# Schematic.net
KiCad netlist of a schematic drawn in Altium Designer
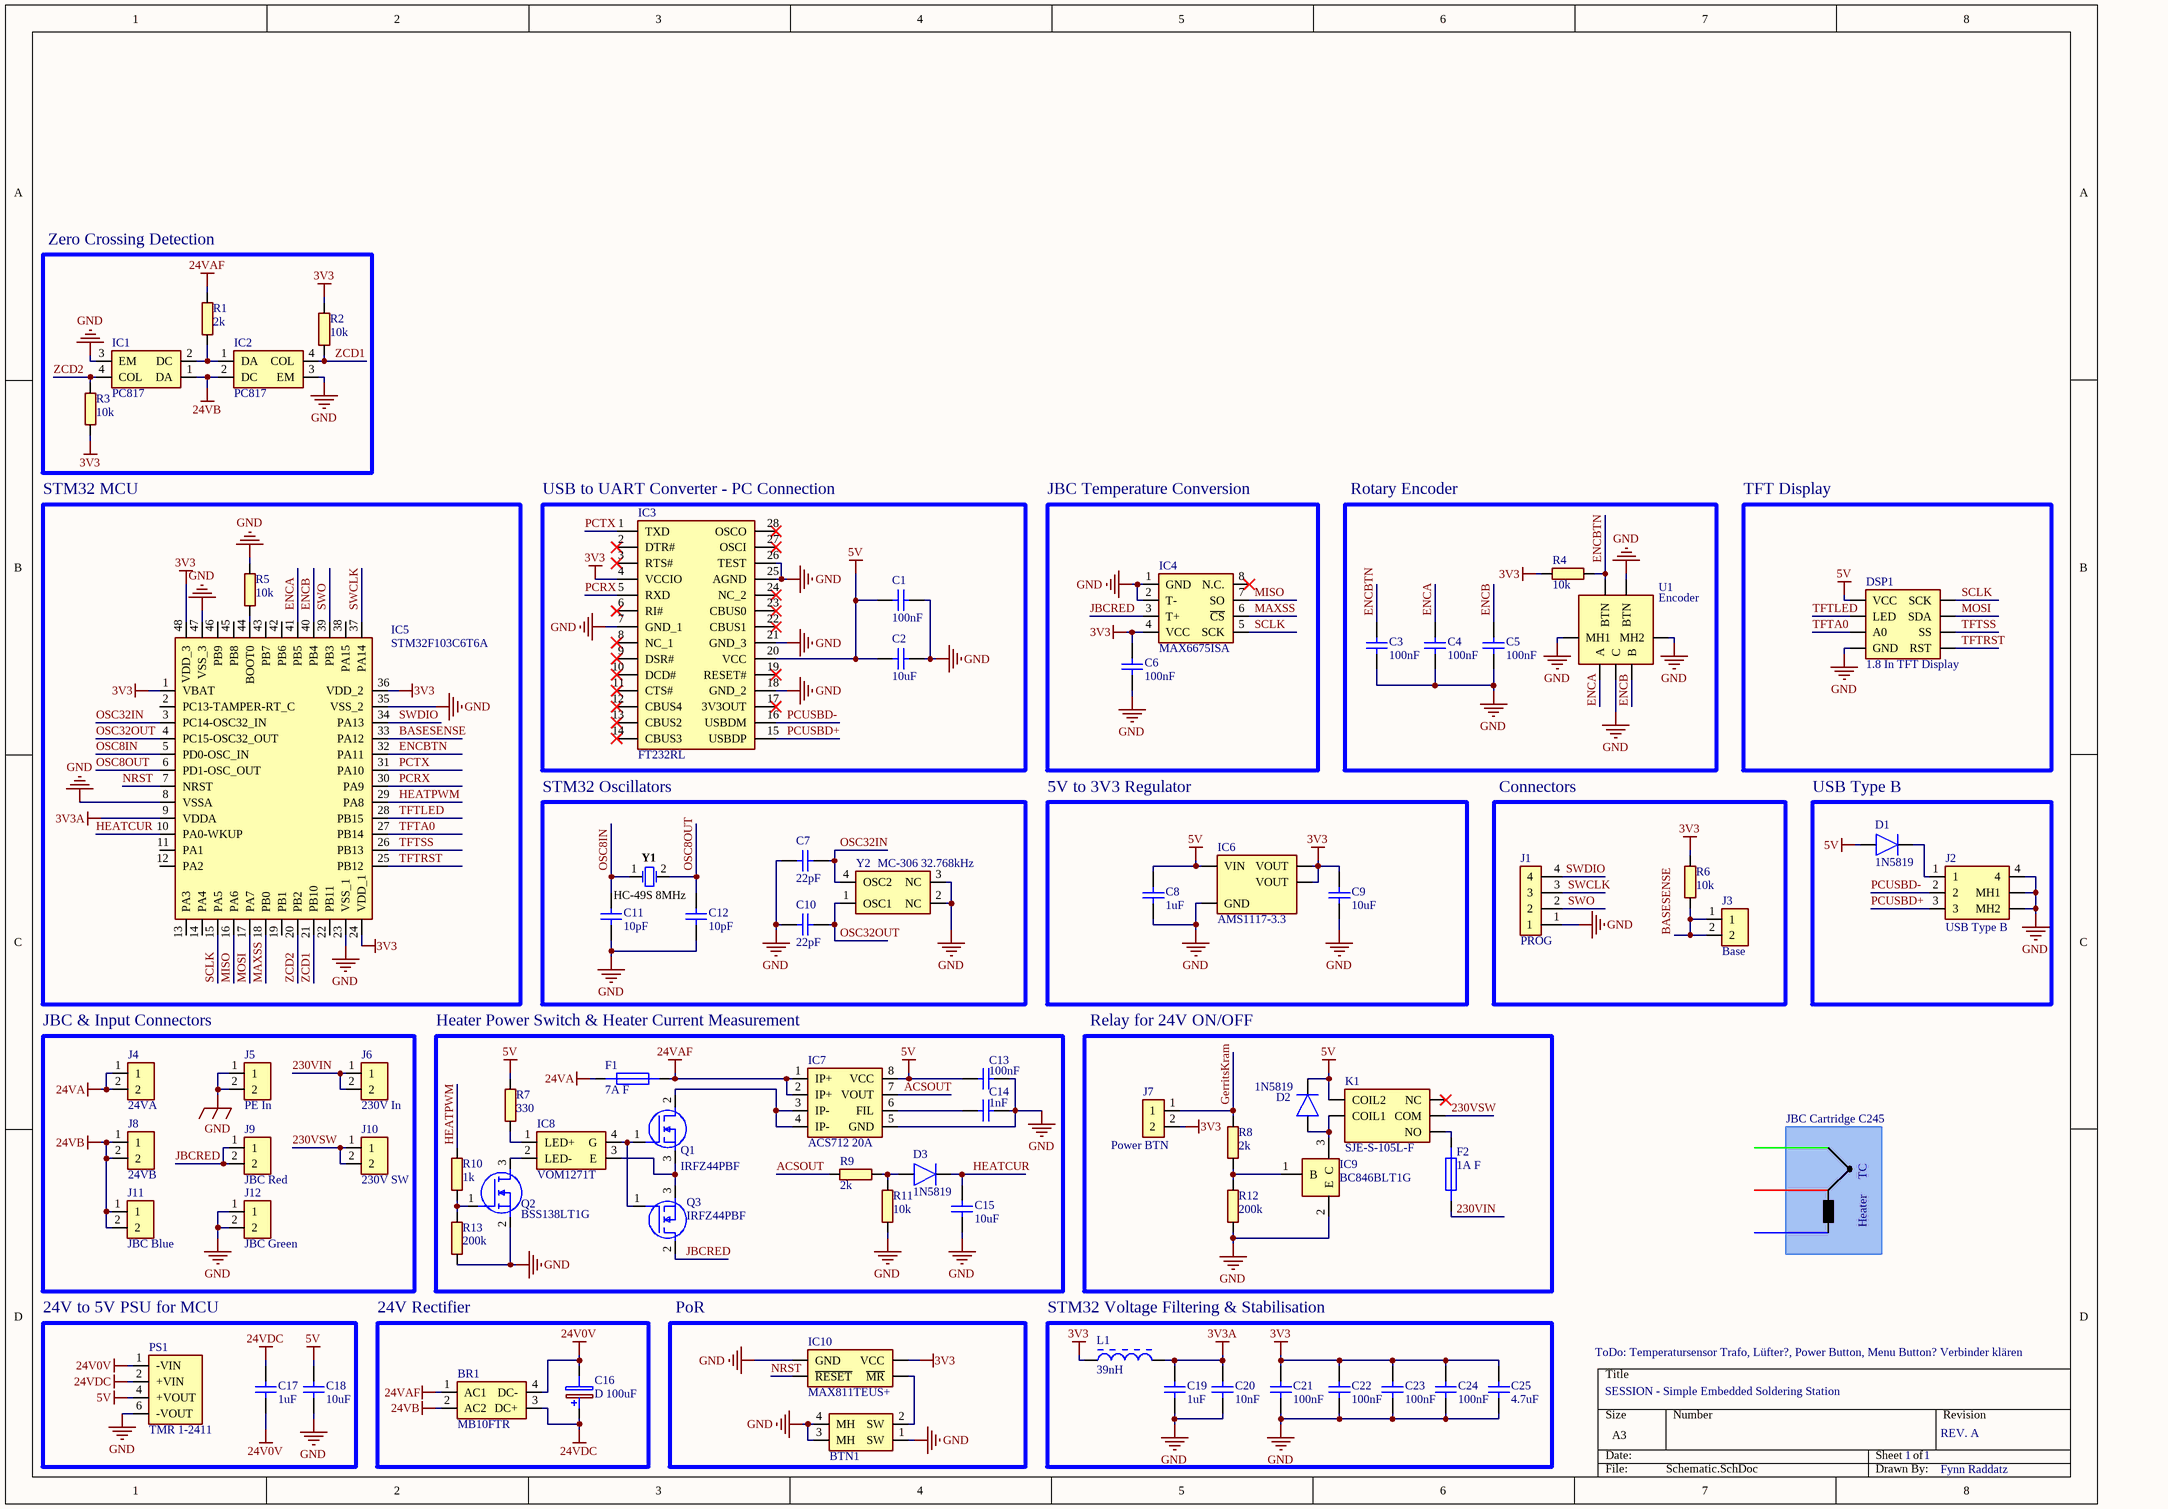
[diagram p0: Schematic.SchDoc]

(export (version "E")
  (design (tool "Eeschema 10.0.6"))
  (components
    (comp (ref "BR1")
      (value "MB10FTR")
      (footprint "SamacSys:SOP250P670X160-4N")
      (description "Bridge Rectifier")
      (libsource (lib "SamacSys") (part "MB10FTR"))
    )
    (comp (ref "BTN1")
      (value "SMD Button 6x6mm Angled")
      (footprint "SMD Button 6x6 Angled")
      (libsource (lib "SamacSys") (part "SMD Button 6x6mm Angled"))
    )
    (comp (ref "C1")
      (value "100nF")
      (footprint "SamacSys:CAPC2012 METRIC")
      (description "Capacitor")
      (fields (field (name "MANUFACTURER_PART_NUMBER") "CL21B104KACNNNC"))
      (libsource (lib "SamacSys") (part "CL21B104KACNNNC"))
    )
    (comp (ref "C2")
      (value "10uF")
      (footprint "SamacSys:CAPC2012 METRIC")
      (description "Capacitor")
      (fields (field (name "MANUFACTURER_PART_NUMBER") "CL21B104KACNNNC"))
      (libsource (lib "SamacSys") (part "CL21B104KACNNNC"))
    )
    (comp (ref "C3")
      (value "100nF")
      (footprint "SamacSys:CAPC2012 METRIC")
      (description "Capacitor")
      (fields (field (name "MANUFACTURER_PART_NUMBER") "CL21B104KACNNNC"))
      (libsource (lib "SamacSys") (part "CL21B104KACNNNC"))
    )
    (comp (ref "C4")
      (value "100nF")
      (footprint "SamacSys:CAPC2012 METRIC")
      (description "Capacitor")
      (fields (field (name "MANUFACTURER_PART_NUMBER") "CL21B104KACNNNC"))
      (libsource (lib "SamacSys") (part "CL21B104KACNNNC"))
    )
    (comp (ref "C5")
      (value "100nF")
      (footprint "SamacSys:CAPC2012 METRIC")
      (description "Capacitor")
      (fields (field (name "MANUFACTURER_PART_NUMBER") "CL21B104KACNNNC"))
      (libsource (lib "SamacSys") (part "CL21B104KACNNNC"))
    )
    (comp (ref "C6")
      (value "100nF")
      (footprint "SamacSys:CAPC2012 METRIC")
      (description "Capacitor")
      (fields (field (name "MANUFACTURER_PART_NUMBER") "CL21B104KACNNNC"))
      (libsource (lib "SamacSys") (part "CL21B104KACNNNC"))
    )
    (comp (ref "C7")
      (value "22pF")
      (footprint "SamacSys:CAPC2012 METRIC")
      (description "Capacitor")
      (fields (field (name "MANUFACTURER_PART_NUMBER") "CL21B104KACNNNC"))
      (libsource (lib "SamacSys") (part "CL21B104KACNNNC"))
    )
    (comp (ref "C8")
      (value "1uF")
      (footprint "SamacSys:CAPC2012 METRIC")
      (description "Capacitor")
      (fields (field (name "MANUFACTURER_PART_NUMBER") "CL21B104KACNNNC"))
      (libsource (lib "SamacSys") (part "CL21B104KACNNNC"))
    )
    (comp (ref "C9")
      (value "10uF")
      (footprint "SamacSys:CAPC2012 METRIC")
      (description "Capacitor")
      (fields (field (name "MANUFACTURER_PART_NUMBER") "CL21B104KACNNNC"))
      (libsource (lib "SamacSys") (part "CL21B104KACNNNC"))
    )
    (comp (ref "C10")
      (value "22pF")
      (footprint "SamacSys:CAPC2012 METRIC")
      (description "Capacitor")
      (fields (field (name "MANUFACTURER_PART_NUMBER") "CL21B104KACNNNC"))
      (libsource (lib "SamacSys") (part "CL21B104KACNNNC"))
    )
    (comp (ref "C11")
      (value "10pF")
      (footprint "SamacSys:CAPC2012 METRIC")
      (description "Capacitor")
      (fields (field (name "MANUFACTURER_PART_NUMBER") "CL21B104KACNNNC"))
      (libsource (lib "SamacSys") (part "CL21B104KACNNNC"))
    )
    (comp (ref "C12")
      (value "10pF")
      (footprint "SamacSys:CAPC2012 METRIC")
      (description "Capacitor")
      (fields (field (name "MANUFACTURER_PART_NUMBER") "CL21B104KACNNNC"))
      (libsource (lib "SamacSys") (part "CL21B104KACNNNC"))
    )
    (comp (ref "C13")
      (value "100nF")
      (footprint "SamacSys:CAPC2012 METRIC")
      (description "Capacitor")
      (fields (field (name "MANUFACTURER_PART_NUMBER") "CL21B104KACNNNC"))
      (libsource (lib "SamacSys") (part "CL21B104KACNNNC"))
    )
    (comp (ref "C14")
      (value "1nF")
      (footprint "SamacSys:CAPC2012 METRIC")
      (description "Capacitor")
      (fields (field (name "MANUFACTURER_PART_NUMBER") "CL21B104KACNNNC"))
      (libsource (lib "SamacSys") (part "CL21B104KACNNNC"))
    )
    (comp (ref "C15")
      (value "10uF")
      (footprint "SamacSys:CAPC2012 METRIC")
      (description "Capacitor")
      (fields (field (name "MANUFACTURER_PART_NUMBER") "CL21B104KACNNNC"))
      (libsource (lib "SamacSys") (part "CL21B104KACNNNC"))
    )
    (comp (ref "C16")
      (value "D 100uF")
      (footprint "TANTAL-D")
      (description "Capacitor Tantalum")
      (libsource (lib "SamacSys") (part "TANTAL-D"))
    )
    (comp (ref "C17")
      (value "1uF")
      (footprint "SamacSys:CAPC2012 METRIC")
      (description "Capacitor")
      (fields (field (name "MANUFACTURER_PART_NUMBER") "CL21B104KACNNNC"))
      (libsource (lib "SamacSys") (part "CL21B104KACNNNC"))
    )
    (comp (ref "C18")
      (value "10uF")
      (footprint "SamacSys:CAPC2012 METRIC")
      (description "Capacitor")
      (fields (field (name "MANUFACTURER_PART_NUMBER") "CL21B104KACNNNC"))
      (libsource (lib "SamacSys") (part "CL21B104KACNNNC"))
    )
    (comp (ref "C19")
      (value "1uF")
      (footprint "SamacSys:CAPC2012 METRIC")
      (description "Capacitor")
      (fields (field (name "MANUFACTURER_PART_NUMBER") "CL21B104KACNNNC"))
      (libsource (lib "SamacSys") (part "CL21B104KACNNNC"))
    )
    (comp (ref "C20")
      (value "10nF")
      (footprint "SamacSys:CAPC2012 METRIC")
      (description "Capacitor")
      (fields (field (name "MANUFACTURER_PART_NUMBER") "CL21B104KACNNNC"))
      (libsource (lib "SamacSys") (part "CL21B104KACNNNC"))
    )
    (comp (ref "C21")
      (value "100nF")
      (footprint "SamacSys:CAPC2012 METRIC")
      (description "Capacitor")
      (fields (field (name "MANUFACTURER_PART_NUMBER") "CL21B104KACNNNC"))
      (libsource (lib "SamacSys") (part "CL21B104KACNNNC"))
    )
    (comp (ref "C22")
      (value "100nF")
      (footprint "SamacSys:CAPC2012 METRIC")
      (description "Capacitor")
      (fields (field (name "MANUFACTURER_PART_NUMBER") "CL21B104KACNNNC"))
      (libsource (lib "SamacSys") (part "CL21B104KACNNNC"))
    )
    (comp (ref "C23")
      (value "100nF")
      (footprint "SamacSys:CAPC2012 METRIC")
      (description "Capacitor")
      (fields (field (name "MANUFACTURER_PART_NUMBER") "CL21B104KACNNNC"))
      (libsource (lib "SamacSys") (part "CL21B104KACNNNC"))
    )
    (comp (ref "C24")
      (value "100nF")
      (footprint "SamacSys:CAPC2012 METRIC")
      (description "Capacitor")
      (fields (field (name "MANUFACTURER_PART_NUMBER") "CL21B104KACNNNC"))
      (libsource (lib "SamacSys") (part "CL21B104KACNNNC"))
    )
    (comp (ref "C25")
      (value "4.7uF")
      (footprint "SamacSys:CAPC2012 METRIC")
      (description "Capacitor")
      (fields (field (name "MANUFACTURER_PART_NUMBER") "CL21B104KACNNNC"))
      (libsource (lib "SamacSys") (part "CL21B104KACNNNC"))
    )
    (comp (ref "D1")
      (value "1N5819")
      (footprint "SamacSys:SOD3716X145N")
      (description "Diode")
      (fields
        (field (name "MANUFACTURER_PART_NUMBER") "1N5819HW-7-F")
        (field (name "MOUSER PART NUMBER") "621-1N5819HW-F")
      )
      (libsource (lib "SamacSys") (part "1N5819HW-7-F"))
    )
    (comp (ref "D2")
      (value "1N5819")
      (footprint "SamacSys:SOD3716X145N")
      (description "Diode")
      (fields
        (field (name "MANUFACTURER_PART_NUMBER") "1N5819HW-7-F")
        (field (name "MOUSER PART NUMBER") "621-1N5819HW-F")
      )
      (libsource (lib "SamacSys") (part "1N5819HW-7-F"))
    )
    (comp (ref "D3")
      (value "1N5819")
      (footprint "SamacSys:SOD3716X145N")
      (description "Diode")
      (fields
        (field (name "MANUFACTURER_PART_NUMBER") "1N5819HW-7-F")
        (field (name "MOUSER PART NUMBER") "621-1N5819HW-F")
      )
      (libsource (lib "SamacSys") (part "1N5819HW-7-F"))
    )
    (comp (ref "DSP1")
      (value "1.8 In TFT Display")
      (footprint "1.8 Inch TFT Display")
      (description "Display")
      (libsource (lib "SamacSys") (part "TFT Display 1.8In SPI"))
    )
    (comp (ref "F1")
      (value "7A F")
      (footprint "Fuse Holder 5x20mm")
      (libsource (lib "SamacSys") (part "Fuse Holder 5x20mm"))
    )
    (comp (ref "F2")
      (value "1A F")
      (footprint "Fuse Holder 5x20mm")
      (libsource (lib "") (part "Fuse Holder 5x20mm_1"))
    )
    (comp (ref "IC1")
      (value "PC817")
      (footprint "SamacSys:SOP254P975X460-4N")
      (description "Integrated Circuit")
      (fields (field (name "MANUFACTURER_PART_NUMBER") "PC817X2NIP0F"))
      (libsource (lib "") (part "PC817X2NIP0F_1"))
    )
    (comp (ref "IC2")
      (value "PC817")
      (footprint "SamacSys:SOP254P975X460-4N")
      (description "Integrated Circuit")
      (fields (field (name "MANUFACTURER_PART_NUMBER") "PC817X2NIP0F"))
      (libsource (lib "SamacSys") (part "PC817X2NIP0F"))
    )
    (comp (ref "IC3")
      (value "FT232RL")
      (footprint "SamacSys:SOP65P778X200-28N")
      (description "Integrated Circuit")
      (libsource (lib "SamacSys") (part "FT232RL"))
    )
    (comp (ref "IC4")
      (value "MAX6675ISA")
      (footprint "SamacSys:SOIC127P600X175-8N")
      (description "Integrated Circuit")
      (libsource (lib "SamacSys") (part "MAX6675ISA"))
    )
    (comp (ref "IC5")
      (value "STM32F103C6T6A")
      (footprint "SamacSys:QFP50P900X900X160-48N")
      (description "Integrated Circuit")
      (fields (field (name "MOUSER PART NUMBER") "511-STM32F103C6T6A"))
      (libsource (lib "SamacSys") (part "STM32F103C6T6A"))
    )
    (comp (ref "IC6")
      (value "AMS1117-3.3")
      (footprint "SamacSys:SOT229P700X180-4N")
      (description "Integrated Circuit")
      (libsource (lib "SamacSys") (part "AMS1117-3.3"))
    )
    (comp (ref "IC7")
      (value "ACS712 20A")
      (footprint "SamacSys:SOIC127P600X175-8N")
      (description "Integrated Circuit")
      (fields (field (name "MANUFACTURER_PART_NUMBER") "ACS712ELCTR-05B-T"))
      (libsource (lib "SamacSys") (part "ACS712ELCTR-05B-T"))
    )
    (comp (ref "IC8")
      (value "VOM1271T")
      (footprint "SamacSys:SOP254P675X240-4N")
      (description "Integrated Circuit")
      (fields (field (name "MOUSER PART NUMBER") "78-VOM1271T"))
      (libsource (lib "SamacSys") (part "VOM1271T"))
    )
    (comp (ref "IC9")
      (value "BC846BLT1G")
      (footprint "SamacSys:SOT96P237X111-3N")
      (description "Integrated Circuit")
      (fields (field (name "MOUSER PART NUMBER") "863-BC846BLT1G"))
      (libsource (lib "SamacSys") (part "BC846BLT1G"))
    )
    (comp (ref "IC10")
      (value "MAX811TEUS+")
      (footprint "SamacSys:MAX811REUST")
      (description "Integrated Circuit")
      (libsource (lib "SamacSys") (part "MAX811TEUS+"))
    )
    (comp (ref "J1")
      (value "PROG")
      (footprint "SamacSys:HDRV4W95P0X254_1X4_1016X254X854P")
      (description "Connector")
      (fields
        (field (name "MANUFACTURER_PART_NUMBER") "61300411121")
        (field (name "MOUSER PART NUMBER") "710-61300411121")
      )
      (libsource (lib "SamacSys") (part "61300411121"))
    )
    (comp (ref "J2")
      (value "USB Type B")
      (footprint "SamacSys:SS52300001")
      (description "Connector")
      (fields
        (field (name "MANUFACTURER_PART_NUMBER") "SS-52300-001")
        (field (name "MOUSER PART NUMBER") "530-SS-52300-001")
      )
      (libsource (lib "SamacSys") (part "USB Type B Connector"))
    )
    (comp (ref "J3")
      (value "Base")
      (footprint "SamacSys:2 Pin Header BIG PADS")
      (description "Connector")
      (fields
        (field (name "MANUFACTURER_PART_NUMBER") "61300211121")
        (field (name "MOUSER PART NUMBER") "710-61300211121")
      )
      (libsource (lib "SamacSys") (part "2 Pin Header Big Pad"))
    )
    (comp (ref "J4")
      (value "24VA")
      (footprint "SamacSys:2 Pin Header BIG PADS")
      (description "Connector")
      (fields
        (field (name "MANUFACTURER_PART_NUMBER") "61300211121")
        (field (name "MOUSER PART NUMBER") "710-61300211121")
      )
      (libsource (lib "SamacSys") (part "2 Pin Header Big Pad"))
    )
    (comp (ref "J5")
      (value "PE In")
      (footprint "SamacSys:2 Pin Header BIG PADS")
      (description "Connector")
      (fields
        (field (name "MANUFACTURER_PART_NUMBER") "61300211121")
        (field (name "MOUSER PART NUMBER") "710-61300211121")
      )
      (libsource (lib "SamacSys") (part "2 Pin Header Big Pad"))
    )
    (comp (ref "J6")
      (value "230V In")
      (footprint "SamacSys:2 Pin Header BIG PADS")
      (description "Connector")
      (fields
        (field (name "MANUFACTURER_PART_NUMBER") "61300211121")
        (field (name "MOUSER PART NUMBER") "710-61300211121")
      )
      (libsource (lib "SamacSys") (part "2 Pin Header Big Pad"))
    )
    (comp (ref "J7")
      (value "Power BTN")
      (footprint "SamacSys:HDRV2W110P0X254_1X2_508X254X854P")
      (description "Connector")
      (fields
        (field (name "MANUFACTURER_PART_NUMBER") "61300211121")
        (field (name "MOUSER PART NUMBER") "710-61300211121")
      )
      (libsource (lib "SamacSys") (part "61300211121"))
    )
    (comp (ref "J8")
      (value "24VB")
      (footprint "SamacSys:2 Pin Header BIG PADS")
      (description "Connector")
      (fields
        (field (name "MANUFACTURER_PART_NUMBER") "61300211121")
        (field (name "MOUSER PART NUMBER") "710-61300211121")
      )
      (libsource (lib "SamacSys") (part "2 Pin Header Big Pad"))
    )
    (comp (ref "J9")
      (value "JBC Red")
      (footprint "SamacSys:2 Pin Header BIG PADS")
      (description "Connector")
      (fields
        (field (name "MANUFACTURER_PART_NUMBER") "61300211121")
        (field (name "MOUSER PART NUMBER") "710-61300211121")
      )
      (libsource (lib "SamacSys") (part "2 Pin Header Big Pad"))
    )
    (comp (ref "J10")
      (value "230V SW")
      (footprint "SamacSys:2 Pin Header BIG PADS")
      (description "Connector")
      (fields
        (field (name "MANUFACTURER_PART_NUMBER") "61300211121")
        (field (name "MOUSER PART NUMBER") "710-61300211121")
      )
      (libsource (lib "SamacSys") (part "2 Pin Header Big Pad"))
    )
    (comp (ref "J11")
      (value "JBC Blue")
      (footprint "SamacSys:2 Pin Header BIG PADS")
      (description "Connector")
      (fields
        (field (name "MANUFACTURER_PART_NUMBER") "61300211121")
        (field (name "MOUSER PART NUMBER") "710-61300211121")
      )
      (libsource (lib "SamacSys") (part "2 Pin Header Big Pad"))
    )
    (comp (ref "J12")
      (value "JBC Green")
      (footprint "SamacSys:2 Pin Header BIG PADS")
      (description "Connector")
      (fields
        (field (name "MANUFACTURER_PART_NUMBER") "61300211121")
        (field (name "MOUSER PART NUMBER") "710-61300211121")
      )
      (libsource (lib "SamacSys") (part "2 Pin Header Big Pad"))
    )
    (comp (ref "K1")
      (value "SJE-S-105L-F")
      (footprint "SamacSys:SJES105LF")
      (description "Relay or Contactor")
      (libsource (lib "SamacSys") (part "SJE-S-105L-F"))
    )
    (comp (ref "L1")
      (value "39nH")
      (footprint "LIRD-LI0805H151R-10-2_V")
      (description "Chip Bead, 100 MHz, 5 A, -40 to 125 degC, 2-Pin SMD (0805), RoHS, Tape and Reel")
      (fields (field (name "MANUFACTURER") "Laird"))
      (libsource (lib "Altium Content Vault") (part "IND-FB-2"))
    )
    (comp (ref "PS1")
      (value "TMR 1-2411")
      (footprint "SamacSys:TMR10511")
      (description "Power Supply")
      (fields (field (name "MOUSER PART NUMBER") "495-TMR-1-2411"))
      (libsource (lib "SamacSys") (part "TMR_1-2411"))
    )
    (comp (ref "Q1")
      (value "IRFZ44PBF")
      (footprint "SamacSys:TO254P465X1024X2050-3P")
      (description "MOSFET (N-Channel)")
      (fields (field (name "MOUSER PART NUMBER") "844-IRFZ44PBF"))
      (libsource (lib "SamacSys") (part "IRFZ44PBF"))
    )
    (comp (ref "Q2")
      (value "BSS138LT1G")
      (footprint "SamacSys:SOT96P237X111-3N")
      (description "MOSFET (N-Channel)")
      (fields (field (name "MOUSER PART NUMBER") "863-BSS138LT1G"))
      (libsource (lib "SamacSys") (part "BSS138LT1G"))
    )
    (comp (ref "Q3")
      (value "IRFZ44PBF")
      (footprint "SamacSys:TO254P465X1024X2050-3P")
      (description "MOSFET (N-Channel)")
      (fields (field (name "MOUSER PART NUMBER") "844-IRFZ44PBF"))
      (libsource (lib "SamacSys") (part "IRFZ44PBF"))
    )
    (comp (ref "R1")
      (value "2k")
      (footprint "SamacSys:RESC2012X65N")
      (description "Resistor")
      (fields (field (name "MANUFACTURER_PART_NUMBER") "RMCF0805ZT0R00"))
      (libsource (lib "SamacSys") (part "Res 0805"))
    )
    (comp (ref "R2")
      (value "10k")
      (footprint "SamacSys:RESC2012X65N")
      (description "Resistor")
      (fields (field (name "MANUFACTURER_PART_NUMBER") "RMCF0805ZT0R00"))
      (libsource (lib "") (part "Res 0805_1"))
    )
    (comp (ref "R3")
      (value "10k")
      (footprint "SamacSys:RESC2012X65N")
      (description "Resistor")
      (fields (field (name "MANUFACTURER_PART_NUMBER") "RMCF0805ZT0R00"))
      (libsource (lib "SamacSys") (part "Res 0805"))
    )
    (comp (ref "R4")
      (value "10k")
      (footprint "SamacSys:RESC2012X65N")
      (description "Resistor")
      (fields (field (name "MANUFACTURER_PART_NUMBER") "RMCF0805ZT0R00"))
      (libsource (lib "") (part "Res 0805_2"))
    )
    (comp (ref "R5")
      (value "10k")
      (footprint "SamacSys:RESC2012X65N")
      (description "Resistor")
      (fields (field (name "MANUFACTURER_PART_NUMBER") "RMCF0805ZT0R00"))
      (libsource (lib "SamacSys") (part "Res 0805"))
    )
    (comp (ref "R6")
      (value "10k")
      (footprint "SamacSys:RESC2012X65N")
      (description "Resistor")
      (fields (field (name "MANUFACTURER_PART_NUMBER") "RMCF0805ZT0R00"))
      (libsource (lib "") (part "Res 0805_1"))
    )
    (comp (ref "R7")
      (value "330")
      (footprint "SamacSys:RESC2012X65N")
      (description "Resistor")
      (fields (field (name "MANUFACTURER_PART_NUMBER") "RMCF0805ZT0R00"))
      (libsource (lib "SamacSys") (part "Res 0805"))
    )
    (comp (ref "R8")
      (value "2k")
      (footprint "SamacSys:RESC2012X65N")
      (description "Resistor")
      (fields (field (name "MANUFACTURER_PART_NUMBER") "RMCF0805ZT0R00"))
      (libsource (lib "SamacSys") (part "Res 0805"))
    )
    (comp (ref "R9")
      (value "2k")
      (footprint "SamacSys:RESC2012X65N")
      (description "Resistor")
      (fields (field (name "MANUFACTURER_PART_NUMBER") "RMCF0805ZT0R00"))
      (libsource (lib "") (part "Res 0805_2"))
    )
    (comp (ref "R10")
      (value "1k")
      (footprint "SamacSys:RESC2012X65N")
      (description "Resistor")
      (fields (field (name "MANUFACTURER_PART_NUMBER") "RMCF0805ZT0R00"))
      (libsource (lib "SamacSys") (part "Res 0805"))
    )
    (comp (ref "R11")
      (value "10k")
      (footprint "SamacSys:RESC2012X65N")
      (description "Resistor")
      (fields (field (name "MANUFACTURER_PART_NUMBER") "RMCF0805ZT0R00"))
      (libsource (lib "") (part "Res 0805_1"))
    )
    (comp (ref "R12")
      (value "200k")
      (footprint "SamacSys:RESC2012X65N")
      (description "Resistor")
      (fields (field (name "MANUFACTURER_PART_NUMBER") "RMCF0805ZT0R00"))
      (libsource (lib "SamacSys") (part "Res 0805"))
    )
    (comp (ref "R13")
      (value "200k")
      (footprint "SamacSys:RESC2012X65N")
      (description "Resistor")
      (fields (field (name "MANUFACTURER_PART_NUMBER") "RMCF0805ZT0R00"))
      (libsource (lib "SamacSys") (part "Res 0805"))
    )
    (comp (ref "U1")
      (value "Encoder")
      (footprint "SamacSys:EC11B152442D")
      (fields (field (name "MANUFACTURER_PART_NUMBER") "EC11B152442D"))
      (libsource (lib "SamacSys") (part "EC11B152442D"))
    )
    (comp (ref "Y1")
      (value "HC-49S 8MHz")
      (footprint "FOX-HC49SDLF_V")
      (description "Resistance Weld Crystal, 8 MHz, +/- 30 ppm, -20 to 70 degC, 2-Pin SMD, RoHS, Tape and Reel")
      (fields (field (name "MANUFACTURER") "FOX Electronics") (field (name "TOLERANCE") "50ppm"))
      (libsource (lib "Altium Content Vault") (part "XTAL-1-2-2"))
    )
    (comp (ref "Y2")
      (value "MC-306 32.768kHz")
      (footprint "SamacSys:MC306327680KA3ROHS")
      (description "Crystal or Oscillator")
      (fields
        (field (name "MANUFACTURER_PART_NUMBER") "MC-306 32.7680K-A3:ROHS")
        (field (name "MOUSER PART NUMBER") "732-MC306-32.7KA3R")
      )
      (libsource (lib "SamacSys") (part "MC-306_32.7680K-A3_ROHS"))
    )
  )
  (nets
    (net (code "1") (name "/230VIN") (class "Default")
      (node (ref "F2") (pin "1") (pinfunction "F1_1") (pintype "passive"))
      (node (ref "J6") (pin "1") (pinfunction "1_1") (pintype "passive"))
      (node (ref "J6") (pin "2") (pinfunction "2_2") (pintype "passive"))
    )
    (net (code "2") (name "/230VSW") (class "Default")
      (node (ref "J10") (pin "1") (pinfunction "1_1") (pintype "passive"))
      (node (ref "J10") (pin "2") (pinfunction "2_2") (pintype "passive"))
      (node (ref "K1") (pin "3") (pinfunction "COM_3") (pintype "passive"))
    )
    (net (code "3") (name "/ACSOUT") (class "Default")
      (node (ref "IC7") (pin "7") (pinfunction "VOUT_7") (pintype "passive"))
      (node (ref "R9") (pin "2") (pinfunction "2_2") (pintype "passive"))
    )
    (net (code "4") (name "/BASESENSE") (class "Default")
      (node (ref "IC5") (pin "33") (pinfunction "PA12_33") (pintype "passive"))
      (node (ref "J3") (pin "1") (pinfunction "1_1") (pintype "passive"))
      (node (ref "J3") (pin "2") (pinfunction "2_2") (pintype "passive"))
      (node (ref "R6") (pin "2") (pinfunction "2_2") (pintype "passive"))
    )
    (net (code "5") (name "/ENCA") (class "Default")
      (node (ref "C4") (pin "2") (pinfunction "2_2") (pintype "passive"))
      (node (ref "IC5") (pin "41") (pinfunction "PB5_41") (pintype "passive"))
      (node (ref "U1") (pin "A") (pinfunction "A_A") (pintype "passive"))
    )
    (net (code "6") (name "/ENCB") (class "Default")
      (node (ref "C5") (pin "2") (pinfunction "2_2") (pintype "passive"))
      (node (ref "IC5") (pin "40") (pinfunction "PB4_40") (pintype "passive"))
      (node (ref "U1") (pin "B") (pinfunction "B_B") (pintype "passive"))
    )
    (net (code "7") (name "/ENCBTN") (class "Default")
      (node (ref "C3") (pin "2") (pinfunction "2_2") (pintype "passive"))
      (node (ref "IC5") (pin "32") (pinfunction "PA11_32") (pintype "passive"))
      (node (ref "R4") (pin "1") (pinfunction "1_1") (pintype "passive"))
      (node (ref "U1") (pin "MH3") (pinfunction "BTN_MH3") (pintype "passive"))
    )
    (net (code "8") (name "/GerritsKram") (class "Default")
      (node (ref "J7") (pin "1") (pinfunction "1_1") (pintype "passive"))
      (node (ref "R8") (pin "2") (pinfunction "2_2") (pintype "passive"))
    )
    (net (code "9") (name "/HEATCUR") (class "Default")
      (node (ref "C15") (pin "1") (pinfunction "1_1") (pintype "passive"))
      (node (ref "D3") (pin "1") (pinfunction "K_1") (pintype "passive"))
      (node (ref "IC5") (pin "10") (pinfunction "PA0-WKUP_10") (pintype "passive"))
    )
    (net (code "10") (name "/HEATPWM") (class "Default")
      (node (ref "IC5") (pin "29") (pinfunction "PA8_29") (pintype "passive"))
      (node (ref "R10") (pin "2") (pinfunction "2_2") (pintype "passive"))
    )
    (net (code "11") (name "/JBCRED") (class "Default")
      (node (ref "IC4") (pin "3") (pinfunction "T+_3") (pintype "passive"))
      (node (ref "J9") (pin "1") (pinfunction "1_1") (pintype "passive"))
      (node (ref "J9") (pin "2") (pinfunction "2_2") (pintype "passive"))
      (node (ref "Q3") (pin "2") (pinfunction "D_2") (pintype "passive"))
    )
    (net (code "12") (name "/MAXSS") (class "Default")
      (node (ref "IC4") (pin "6") (pinfunction "~{CS}_6") (pintype "passive"))
      (node (ref "IC5") (pin "18") (pinfunction "PB0_18") (pintype "passive"))
    )
    (net (code "13") (name "/MISO") (class "Default")
      (node (ref "IC4") (pin "7") (pinfunction "SO_7") (pintype "passive"))
      (node (ref "IC5") (pin "16") (pinfunction "PA6_16") (pintype "passive"))
    )
    (net (code "14") (name "/MOSI") (class "Default")
      (node (ref "DSP1") (pin "3") (pinfunction "SDA_3") (pintype "passive"))
      (node (ref "IC5") (pin "17") (pinfunction "PA7_17") (pintype "passive"))
    )
    (net (code "15") (name "/NRST") (class "Default")
      (node (ref "IC10") (pin "2") (pinfunction "~{RESET}_2") (pintype "passive"))
      (node (ref "IC5") (pin "7") (pinfunction "NRST_7") (pintype "passive"))
    )
    (net (code "16") (name "/OSC8IN") (class "Default")
      (node (ref "C11") (pin "2") (pinfunction "2_2") (pintype "passive"))
      (node (ref "IC5") (pin "5") (pinfunction "PD0-OSC_IN_5") (pintype "passive"))
      (node (ref "Y1") (pin "1") (pinfunction "1_1") (pintype "passive"))
    )
    (net (code "17") (name "/OSC8OUT") (class "Default")
      (node (ref "C12") (pin "2") (pinfunction "2_2") (pintype "passive"))
      (node (ref "IC5") (pin "6") (pinfunction "PD1-OSC_OUT_6") (pintype "passive"))
      (node (ref "Y1") (pin "2") (pinfunction "2_2") (pintype "passive"))
    )
    (net (code "18") (name "/OSC32IN") (class "Default")
      (node (ref "C7") (pin "1") (pinfunction "1_1") (pintype "passive"))
      (node (ref "IC5") (pin "3") (pinfunction "PC14-OSC32_IN_3") (pintype "passive"))
      (node (ref "Y2") (pin "4") (pinfunction "OSC2_4") (pintype "passive"))
    )
    (net (code "19") (name "/OSC32OUT") (class "Default")
      (node (ref "C10") (pin "1") (pinfunction "1_1") (pintype "passive"))
      (node (ref "IC5") (pin "4") (pinfunction "PC15-OSC32_OUT_4") (pintype "passive"))
      (node (ref "Y2") (pin "1") (pinfunction "OSC1_1") (pintype "passive"))
    )
    (net (code "20") (name "/PCRX") (class "Default")
      (node (ref "IC3") (pin "5") (pinfunction "RXD_5") (pintype "passive"))
      (node (ref "IC5") (pin "30") (pinfunction "PA9_30") (pintype "passive"))
    )
    (net (code "21") (name "/PCTX") (class "Default")
      (node (ref "IC3") (pin "1") (pinfunction "TXD_1") (pintype "passive"))
      (node (ref "IC5") (pin "31") (pinfunction "PA10_31") (pintype "passive"))
    )
    (net (code "22") (name "/PCUSBD+") (class "Default")
      (node (ref "IC3") (pin "15") (pinfunction "USBDP_15") (pintype "passive"))
      (node (ref "J2") (pin "3") (pinfunction "3_3") (pintype "passive"))
    )
    (net (code "23") (name "/PCUSBD-") (class "Default")
      (node (ref "IC3") (pin "16") (pinfunction "USBDM_16") (pintype "passive"))
      (node (ref "J2") (pin "2") (pinfunction "2_2") (pintype "passive"))
    )
    (net (code "24") (name "/SCLK") (class "Default")
      (node (ref "DSP1") (pin "2") (pinfunction "SCK_2") (pintype "passive"))
      (node (ref "IC4") (pin "5") (pinfunction "SCK_5") (pintype "passive"))
      (node (ref "IC5") (pin "15") (pinfunction "PA5_15") (pintype "passive"))
    )
    (net (code "25") (name "/SWCLK") (class "Default")
      (node (ref "IC5") (pin "37") (pinfunction "PA14_37") (pintype "passive"))
      (node (ref "J1") (pin "3") (pinfunction "3_3") (pintype "passive"))
    )
    (net (code "26") (name "/SWDIO") (class "Default")
      (node (ref "IC5") (pin "34") (pinfunction "PA13_34") (pintype "passive"))
      (node (ref "J1") (pin "4") (pinfunction "4_4") (pintype "passive"))
    )
    (net (code "27") (name "/SWO") (class "Default")
      (node (ref "IC5") (pin "39") (pinfunction "PB3_39") (pintype "passive"))
      (node (ref "J1") (pin "2") (pinfunction "2_2") (pintype "passive"))
    )
    (net (code "28") (name "/TFTA0") (class "Default")
      (node (ref "DSP1") (pin "4") (pinfunction "A0_4") (pintype "passive"))
      (node (ref "IC5") (pin "27") (pinfunction "PB14_27") (pintype "passive"))
    )
    (net (code "29") (name "/TFTLED") (class "Default")
      (node (ref "DSP1") (pin "1") (pinfunction "LED_1") (pintype "passive"))
      (node (ref "IC5") (pin "28") (pinfunction "PB15_28") (pintype "passive"))
    )
    (net (code "30") (name "/TFTRST") (class "Default")
      (node (ref "DSP1") (pin "5") (pinfunction "RST_5") (pintype "passive"))
      (node (ref "IC5") (pin "25") (pinfunction "PB12_25") (pintype "passive"))
    )
    (net (code "31") (name "/TFTSS") (class "Default")
      (node (ref "DSP1") (pin "6") (pinfunction "SS_6") (pintype "passive"))
      (node (ref "IC5") (pin "26") (pinfunction "PB13_26") (pintype "passive"))
    )
    (net (code "32") (name "/ZCD1") (class "Default")
      (node (ref "IC2") (pin "4") (pinfunction "COL_4") (pintype "passive"))
      (node (ref "IC5") (pin "21") (pinfunction "PB10_21") (pintype "passive"))
      (node (ref "R2") (pin "2") (pinfunction "2_2") (pintype "passive"))
    )
    (net (code "33") (name "/ZCD2") (class "Default")
      (node (ref "IC1") (pin "4") (pinfunction "COL_4") (pintype "passive"))
      (node (ref "IC5") (pin "20") (pinfunction "PB2_20") (pintype "passive"))
      (node (ref "R3") (pin "2") (pinfunction "2_2") (pintype "passive"))
    )
    (net (code "34") (name "3V3") (class "Default")
      (node (ref "C21") (pin "2") (pinfunction "2_2") (pintype "passive"))
      (node (ref "C22") (pin "2") (pinfunction "2_2") (pintype "passive"))
      (node (ref "C23") (pin "2") (pinfunction "2_2") (pintype "passive"))
      (node (ref "C24") (pin "2") (pinfunction "2_2") (pintype "passive"))
      (node (ref "C25") (pin "2") (pinfunction "2_2") (pintype "passive"))
      (node (ref "C6") (pin "2") (pinfunction "2_2") (pintype "passive"))
      (node (ref "C9") (pin "1") (pinfunction "1_1") (pintype "passive"))
      (node (ref "IC10") (pin "4") (pinfunction "VCC_4") (pintype "passive"))
      (node (ref "IC3") (pin "4") (pinfunction "VCCIO_4") (pintype "passive"))
      (node (ref "IC4") (pin "4") (pinfunction "VCC_4") (pintype "passive"))
      (node (ref "IC5") (pin "1") (pinfunction "VBAT_1") (pintype "passive"))
      (node (ref "IC5") (pin "24") (pinfunction "VDD_1_24") (pintype "passive"))
      (node (ref "IC5") (pin "36") (pinfunction "VDD_2_36") (pintype "passive"))
      (node (ref "IC5") (pin "48") (pinfunction "VDD_3_48") (pintype "passive"))
      (node (ref "IC6") (pin "2") (pinfunction "VOUT_2") (pintype "passive"))
      (node (ref "IC6") (pin "4") (pinfunction "VOUT_4") (pintype "passive"))
      (node (ref "J7") (pin "2") (pinfunction "2_2") (pintype "passive"))
      (node (ref "L1") (pin "1") (pinfunction "1_1") (pintype "passive"))
      (node (ref "R2") (pin "1") (pinfunction "1_1") (pintype "passive"))
      (node (ref "R3") (pin "1") (pinfunction "1_1") (pintype "passive"))
      (node (ref "R4") (pin "2") (pinfunction "2_2") (pintype "passive"))
      (node (ref "R6") (pin "1") (pinfunction "1_1") (pintype "passive"))
    )
    (net (code "35") (name "3V3A") (class "Default")
      (node (ref "C19") (pin "2") (pinfunction "2_2") (pintype "passive"))
      (node (ref "C20") (pin "2") (pinfunction "2_2") (pintype "passive"))
      (node (ref "IC5") (pin "9") (pinfunction "VDDA_9") (pintype "passive"))
      (node (ref "L1") (pin "2") (pinfunction "2_2") (pintype "passive"))
    )
    (net (code "36") (name "5V") (class "Default")
      (node (ref "C1") (pin "1") (pinfunction "1_1") (pintype "passive"))
      (node (ref "C13") (pin "2") (pinfunction "2_2") (pintype "passive"))
      (node (ref "C18") (pin "2") (pinfunction "2_2") (pintype "passive"))
      (node (ref "C2") (pin "1") (pinfunction "1_1") (pintype "passive"))
      (node (ref "C8") (pin "1") (pinfunction "1_1") (pintype "passive"))
      (node (ref "D1") (pin "2") (pinfunction "A_2") (pintype "passive"))
      (node (ref "D2") (pin "1") (pinfunction "K_1") (pintype "passive"))
      (node (ref "DSP1") (pin "8") (pinfunction "VCC_8") (pintype "passive"))
      (node (ref "IC3") (pin "20") (pinfunction "VCC_20") (pintype "passive"))
      (node (ref "IC6") (pin "3") (pinfunction "VIN_3") (pintype "passive"))
      (node (ref "IC7") (pin "8") (pinfunction "VCC_8") (pintype "passive"))
      (node (ref "K1") (pin "2") (pinfunction "COIL2_2") (pintype "passive"))
      (node (ref "PS1") (pin "4") (pinfunction "+VOUT_4") (pintype "passive"))
      (node (ref "R7") (pin "2") (pinfunction "2_2") (pintype "passive"))
    )
    (net (code "37") (name "24V0V") (class "Default")
      (node (ref "BR1") (pin "4") (pinfunction "DC-_4") (pintype "passive"))
      (node (ref "C16") (pin "2") (pinfunction "-_2") (pintype "passive"))
      (node (ref "C17") (pin "1") (pinfunction "1_1") (pintype "passive"))
      (node (ref "PS1") (pin "1") (pinfunction "-VIN_1") (pintype "passive"))
    )
    (net (code "38") (name "24VA") (class "Default")
      (node (ref "F1") (pin "1") (pinfunction "F1_1") (pintype "passive"))
      (node (ref "J4") (pin "1") (pinfunction "1_1") (pintype "passive"))
      (node (ref "J4") (pin "2") (pinfunction "2_2") (pintype "passive"))
    )
    (net (code "39") (name "24VAF") (class "Default")
      (node (ref "BR1") (pin "1") (pinfunction "AC1_1") (pintype "passive"))
      (node (ref "F1") (pin "2") (pinfunction "F2_2") (pintype "passive"))
      (node (ref "IC7") (pin "1") (pinfunction "IP+_1") (pintype "passive"))
      (node (ref "IC7") (pin "2") (pinfunction "IP+_2") (pintype "passive"))
      (node (ref "R1") (pin "2") (pinfunction "2_2") (pintype "passive"))
    )
    (net (code "40") (name "24VB") (class "Default")
      (node (ref "BR1") (pin "2") (pinfunction "AC2_2") (pintype "passive"))
      (node (ref "IC1") (pin "1") (pinfunction "DA_1") (pintype "passive"))
      (node (ref "IC2") (pin "2") (pinfunction "DC_2") (pintype "passive"))
      (node (ref "J11") (pin "1") (pinfunction "1_1") (pintype "passive"))
      (node (ref "J11") (pin "2") (pinfunction "2_2") (pintype "passive"))
      (node (ref "J8") (pin "1") (pinfunction "1_1") (pintype "passive"))
      (node (ref "J8") (pin "2") (pinfunction "2_2") (pintype "passive"))
    )
    (net (code "41") (name "24VDC") (class "Default")
      (node (ref "BR1") (pin "3") (pinfunction "DC+_3") (pintype "passive"))
      (node (ref "C16") (pin "1") (pinfunction "+_1") (pintype "passive"))
      (node (ref "C17") (pin "2") (pinfunction "2_2") (pintype "passive"))
      (node (ref "PS1") (pin "2") (pinfunction "+VIN_2") (pintype "passive"))
    )
    (net (code "42") (name "GND") (class "Default")
      (node (ref "BTN1") (pin "1") (pinfunction "SW_1") (pintype "passive"))
      (node (ref "BTN1") (pin "3") (pinfunction "MH_3") (pintype "passive"))
      (node (ref "BTN1") (pin "4") (pinfunction "MH_4") (pintype "passive"))
      (node (ref "C1") (pin "2") (pinfunction "2_2") (pintype "passive"))
      (node (ref "C10") (pin "2") (pinfunction "2_2") (pintype "passive"))
      (node (ref "C11") (pin "1") (pinfunction "1_1") (pintype "passive"))
      (node (ref "C12") (pin "1") (pinfunction "1_1") (pintype "passive"))
      (node (ref "C13") (pin "1") (pinfunction "1_1") (pintype "passive"))
      (node (ref "C14") (pin "1") (pinfunction "1_1") (pintype "passive"))
      (node (ref "C15") (pin "2") (pinfunction "2_2") (pintype "passive"))
      (node (ref "C18") (pin "1") (pinfunction "1_1") (pintype "passive"))
      (node (ref "C19") (pin "1") (pinfunction "1_1") (pintype "passive"))
      (node (ref "C2") (pin "2") (pinfunction "2_2") (pintype "passive"))
      (node (ref "C20") (pin "1") (pinfunction "1_1") (pintype "passive"))
      (node (ref "C21") (pin "1") (pinfunction "1_1") (pintype "passive"))
      (node (ref "C22") (pin "1") (pinfunction "1_1") (pintype "passive"))
      (node (ref "C23") (pin "1") (pinfunction "1_1") (pintype "passive"))
      (node (ref "C24") (pin "1") (pinfunction "1_1") (pintype "passive"))
      (node (ref "C25") (pin "1") (pinfunction "1_1") (pintype "passive"))
      (node (ref "C3") (pin "1") (pinfunction "1_1") (pintype "passive"))
      (node (ref "C4") (pin "1") (pinfunction "1_1") (pintype "passive"))
      (node (ref "C5") (pin "1") (pinfunction "1_1") (pintype "passive"))
      (node (ref "C6") (pin "1") (pinfunction "1_1") (pintype "passive"))
      (node (ref "C7") (pin "2") (pinfunction "2_2") (pintype "passive"))
      (node (ref "C8") (pin "2") (pinfunction "2_2") (pintype "passive"))
      (node (ref "C9") (pin "2") (pinfunction "2_2") (pintype "passive"))
      (node (ref "DSP1") (pin "7") (pinfunction "GND_7") (pintype "passive"))
      (node (ref "IC1") (pin "3") (pinfunction "EM_3") (pintype "passive"))
      (node (ref "IC10") (pin "1") (pinfunction "GND_1") (pintype "passive"))
      (node (ref "IC2") (pin "3") (pinfunction "EM_3") (pintype "passive"))
      (node (ref "IC3") (pin "18") (pinfunction "GND_2_18") (pintype "passive"))
      (node (ref "IC3") (pin "21") (pinfunction "GND_3_21") (pintype "passive"))
      (node (ref "IC3") (pin "25") (pinfunction "AGND_25") (pintype "passive"))
      (node (ref "IC3") (pin "26") (pinfunction "TEST_26") (pintype "passive"))
      (node (ref "IC3") (pin "7") (pinfunction "GND_1_7") (pintype "passive"))
      (node (ref "IC4") (pin "1") (pinfunction "GND_1") (pintype "passive"))
      (node (ref "IC4") (pin "2") (pinfunction "T-_2") (pintype "passive"))
      (node (ref "IC5") (pin "23") (pinfunction "VSS_1_23") (pintype "passive"))
      (node (ref "IC5") (pin "35") (pinfunction "VSS_2_35") (pintype "passive"))
      (node (ref "IC5") (pin "47") (pinfunction "VSS_3_47") (pintype "passive"))
      (node (ref "IC5") (pin "8") (pinfunction "VSSA_8") (pintype "passive"))
      (node (ref "IC6") (pin "1") (pinfunction "GND_1") (pintype "passive"))
      (node (ref "IC7") (pin "5") (pinfunction "GND_5") (pintype "passive"))
      (node (ref "IC9") (pin "2") (pinfunction "E_2") (pintype "passive"))
      (node (ref "J1") (pin "1") (pinfunction "1_1") (pintype "passive"))
      (node (ref "J12") (pin "1") (pinfunction "1_1") (pintype "passive"))
      (node (ref "J12") (pin "2") (pinfunction "2_2") (pintype "passive"))
      (node (ref "J2") (pin "4") (pinfunction "4_4") (pintype "passive"))
      (node (ref "J2") (pin "MH1") (pinfunction "MH1_MH1") (pintype "passive"))
      (node (ref "J2") (pin "MH2") (pinfunction "MH2_MH2") (pintype "passive"))
      (node (ref "J5") (pin "1") (pinfunction "1_1") (pintype "passive"))
      (node (ref "J5") (pin "2") (pinfunction "2_2") (pintype "passive"))
      (node (ref "PS1") (pin "6") (pinfunction "-VOUT_6") (pintype "passive"))
      (node (ref "Q2") (pin "2") (pinfunction "S_2") (pintype "passive"))
      (node (ref "R11") (pin "2") (pinfunction "2_2") (pintype "passive"))
      (node (ref "R12") (pin "1") (pinfunction "1_1") (pintype "passive"))
      (node (ref "R13") (pin "1") (pinfunction "1_1") (pintype "passive"))
      (node (ref "R5") (pin "2") (pinfunction "2_2") (pintype "passive"))
      (node (ref "U1") (pin "C") (pinfunction "C_C") (pintype "passive"))
      (node (ref "U1") (pin "MH1") (pinfunction "MH1_MH1") (pintype "passive"))
      (node (ref "U1") (pin "MH2") (pinfunction "MH2_MH2") (pintype "passive"))
      (node (ref "U1") (pin "MH4") (pinfunction "BTN_MH4") (pintype "passive"))
      (node (ref "Y2") (pin "2") (pinfunction "NC_2") (pintype "passive"))
      (node (ref "Y2") (pin "3") (pinfunction "NC_3") (pintype "passive"))
    )
    (net (code "43") (name "Net-(D1-K)") (class "Default")
      (node (ref "D1") (pin "1") (pinfunction "K_1") (pintype "passive"))
      (node (ref "J2") (pin "1") (pinfunction "1_1") (pintype "passive"))
    )
    (net (code "44") (name "Net-(D2-A)") (class "Default")
      (node (ref "D2") (pin "2") (pinfunction "A_2") (pintype "passive"))
      (node (ref "IC9") (pin "3") (pinfunction "C_3") (pintype "passive"))
      (node (ref "K1") (pin "1") (pinfunction "COIL1_1") (pintype "passive"))
    )
    (net (code "45") (name "Net-(D3-A)") (class "Default")
      (node (ref "D3") (pin "2") (pinfunction "A_2") (pintype "passive"))
      (node (ref "R11") (pin "1") (pinfunction "1_1") (pintype "passive"))
      (node (ref "R9") (pin "1") (pinfunction "1_1") (pintype "passive"))
    )
    (net (code "46") (name "Net-(F2-F2)") (class "Default")
      (node (ref "F2") (pin "2") (pinfunction "F2_2") (pintype "passive"))
      (node (ref "K1") (pin "4") (pinfunction "NO_4") (pintype "passive"))
    )
    (net (code "47") (name "Net-(IC1-DC)") (class "Default")
      (node (ref "IC1") (pin "2") (pinfunction "DC_2") (pintype "passive"))
      (node (ref "IC2") (pin "1") (pinfunction "DA_1") (pintype "passive"))
      (node (ref "R1") (pin "1") (pinfunction "1_1") (pintype "passive"))
    )
    (net (code "48") (name "Net-(IC5-BOOT0)") (class "Default")
      (node (ref "IC5") (pin "44") (pinfunction "BOOT0_44") (pintype "passive"))
      (node (ref "R5") (pin "1") (pinfunction "1_1") (pintype "passive"))
    )
    (net (code "49") (name "Net-(IC7-FIL)") (class "Default")
      (node (ref "C14") (pin "2") (pinfunction "2_2") (pintype "passive"))
      (node (ref "IC7") (pin "6") (pinfunction "FIL_6") (pintype "passive"))
    )
    (net (code "50") (name "Net-(IC8-E)") (class "Default")
      (node (ref "IC8") (pin "3") (pinfunction "E_3") (pintype "passive"))
      (node (ref "Q1") (pin "3") (pinfunction "S_3") (pintype "passive"))
      (node (ref "Q3") (pin "3") (pinfunction "S_3") (pintype "passive"))
    )
    (net (code "51") (name "Net-(IC8-G)") (class "Default")
      (node (ref "IC8") (pin "4") (pinfunction "G_4") (pintype "passive"))
      (node (ref "Q1") (pin "1") (pinfunction "G_1") (pintype "passive"))
      (node (ref "Q3") (pin "1") (pinfunction "G_1") (pintype "passive"))
    )
    (net (code "52") (name "Net-(IC8-LED+)") (class "Default")
      (node (ref "IC8") (pin "1") (pinfunction "LED+_1") (pintype "passive"))
      (node (ref "R7") (pin "1") (pinfunction "1_1") (pintype "passive"))
    )
    (net (code "53") (name "Net-(IC8-LED-)") (class "Default")
      (node (ref "IC8") (pin "2") (pinfunction "LED-_2") (pintype "passive"))
      (node (ref "Q2") (pin "3") (pinfunction "D_3") (pintype "passive"))
    )
    (net (code "54") (name "Net-(IC9-B)") (class "Default")
      (node (ref "IC9") (pin "1") (pinfunction "B_1") (pintype "passive"))
      (node (ref "R12") (pin "2") (pinfunction "2_2") (pintype "passive"))
      (node (ref "R8") (pin "1") (pinfunction "1_1") (pintype "passive"))
    )
    (net (code "55") (name "Net-(IC10-~{MR})") (class "Default")
      (node (ref "BTN1") (pin "2") (pinfunction "SW_2") (pintype "passive"))
      (node (ref "IC10") (pin "3") (pinfunction "~{MR}_3") (pintype "passive"))
    )
    (net (code "56") (name "Net-(Q1-D)") (class "Default")
      (node (ref "IC7") (pin "3") (pinfunction "IP-_3") (pintype "passive"))
      (node (ref "IC7") (pin "4") (pinfunction "IP-_4") (pintype "passive"))
      (node (ref "Q1") (pin "2") (pinfunction "D_2") (pintype "passive"))
    )
    (net (code "57") (name "Net-(Q2-G)") (class "Default")
      (node (ref "Q2") (pin "1") (pinfunction "G_1") (pintype "passive"))
      (node (ref "R10") (pin "1") (pinfunction "1_1") (pintype "passive"))
      (node (ref "R13") (pin "2") (pinfunction "2_2") (pintype "passive"))
    )
    (net (code "58") (name "unconnected-(IC3-3V3OUT-Pad17)") (class "Default")
      (node (ref "IC3") (pin "17") (pinfunction "3V3OUT_17") (pintype "passive+no_connect"))
    )
    (net (code "59") (name "unconnected-(IC3-CBUS0-Pad23)") (class "Default")
      (node (ref "IC3") (pin "23") (pinfunction "CBUS0_23") (pintype "passive+no_connect"))
    )
    (net (code "60") (name "unconnected-(IC3-CBUS1-Pad22)") (class "Default")
      (node (ref "IC3") (pin "22") (pinfunction "CBUS1_22") (pintype "passive+no_connect"))
    )
    (net (code "61") (name "unconnected-(IC3-CBUS2-Pad13)") (class "Default")
      (node (ref "IC3") (pin "13") (pinfunction "CBUS2_13") (pintype "passive+no_connect"))
    )
    (net (code "62") (name "unconnected-(IC3-CBUS3-Pad14)") (class "Default")
      (node (ref "IC3") (pin "14") (pinfunction "CBUS3_14") (pintype "passive+no_connect"))
    )
    (net (code "63") (name "unconnected-(IC3-CBUS4-Pad12)") (class "Default")
      (node (ref "IC3") (pin "12") (pinfunction "CBUS4_12") (pintype "passive+no_connect"))
    )
    (net (code "64") (name "unconnected-(IC3-CTS#-Pad11)") (class "Default")
      (node (ref "IC3") (pin "11") (pinfunction "CTS#_11") (pintype "passive+no_connect"))
    )
    (net (code "65") (name "unconnected-(IC3-DCD#-Pad10)") (class "Default")
      (node (ref "IC3") (pin "10") (pinfunction "DCD#_10") (pintype "passive+no_connect"))
    )
    (net (code "66") (name "unconnected-(IC3-DSR#-Pad9)") (class "Default")
      (node (ref "IC3") (pin "9") (pinfunction "DSR#_9") (pintype "passive+no_connect"))
    )
    (net (code "67") (name "unconnected-(IC3-DTR#-Pad2)") (class "Default")
      (node (ref "IC3") (pin "2") (pinfunction "DTR#_2") (pintype "passive+no_connect"))
    )
    (net (code "68") (name "unconnected-(IC3-NC_1-Pad8)") (class "Default")
      (node (ref "IC3") (pin "8") (pinfunction "NC_1_8") (pintype "passive+no_connect"))
    )
    (net (code "69") (name "unconnected-(IC3-NC_2-Pad24)") (class "Default")
      (node (ref "IC3") (pin "24") (pinfunction "NC_2_24") (pintype "passive+no_connect"))
    )
    (net (code "70") (name "unconnected-(IC3-OSCI-Pad27)") (class "Default")
      (node (ref "IC3") (pin "27") (pinfunction "OSCI_27") (pintype "passive+no_connect"))
    )
    (net (code "71") (name "unconnected-(IC3-OSCO-Pad28)") (class "Default")
      (node (ref "IC3") (pin "28") (pinfunction "OSCO_28") (pintype "passive+no_connect"))
    )
    (net (code "72") (name "unconnected-(IC3-RESET#-Pad19)") (class "Default")
      (node (ref "IC3") (pin "19") (pinfunction "RESET#_19") (pintype "passive+no_connect"))
    )
    (net (code "73") (name "unconnected-(IC3-RI#-Pad6)") (class "Default")
      (node (ref "IC3") (pin "6") (pinfunction "RI#_6") (pintype "passive+no_connect"))
    )
    (net (code "74") (name "unconnected-(IC3-RTS#-Pad3)") (class "Default")
      (node (ref "IC3") (pin "3") (pinfunction "RTS#_3") (pintype "passive+no_connect"))
    )
    (net (code "75") (name "unconnected-(IC4-N.C.-Pad8)") (class "Default")
      (node (ref "IC4") (pin "8") (pinfunction "N.C._8") (pintype "passive+no_connect"))
    )
    (net (code "76") (name "unconnected-(IC5-PA1-Pad11)") (class "Default")
      (node (ref "IC5") (pin "11") (pinfunction "PA1_11") (pintype "passive"))
    )
    (net (code "77") (name "unconnected-(IC5-PA2-Pad12)") (class "Default")
      (node (ref "IC5") (pin "12") (pinfunction "PA2_12") (pintype "passive"))
    )
    (net (code "78") (name "unconnected-(IC5-PA3-Pad13)") (class "Default")
      (node (ref "IC5") (pin "13") (pinfunction "PA3_13") (pintype "passive"))
    )
    (net (code "79") (name "unconnected-(IC5-PA4-Pad14)") (class "Default")
      (node (ref "IC5") (pin "14") (pinfunction "PA4_14") (pintype "passive"))
    )
    (net (code "80") (name "unconnected-(IC5-PA15-Pad38)") (class "Default")
      (node (ref "IC5") (pin "38") (pinfunction "PA15_38") (pintype "passive"))
    )
    (net (code "81") (name "unconnected-(IC5-PB1-Pad19)") (class "Default")
      (node (ref "IC5") (pin "19") (pinfunction "PB1_19") (pintype "passive"))
    )
    (net (code "82") (name "unconnected-(IC5-PB6-Pad42)") (class "Default")
      (node (ref "IC5") (pin "42") (pinfunction "PB6_42") (pintype "passive"))
    )
    (net (code "83") (name "unconnected-(IC5-PB7-Pad43)") (class "Default")
      (node (ref "IC5") (pin "43") (pinfunction "PB7_43") (pintype "passive"))
    )
    (net (code "84") (name "unconnected-(IC5-PB8-Pad45)") (class "Default")
      (node (ref "IC5") (pin "45") (pinfunction "PB8_45") (pintype "passive"))
    )
    (net (code "85") (name "unconnected-(IC5-PB9-Pad46)") (class "Default")
      (node (ref "IC5") (pin "46") (pinfunction "PB9_46") (pintype "passive"))
    )
    (net (code "86") (name "unconnected-(IC5-PB11-Pad22)") (class "Default")
      (node (ref "IC5") (pin "22") (pinfunction "PB11_22") (pintype "passive"))
    )
    (net (code "87") (name "unconnected-(IC5-PC13-TAMPER-RT_C-Pad2)") (class "Default")
      (node (ref "IC5") (pin "2") (pinfunction "PC13-TAMPER-RT_C_2") (pintype "passive"))
    )
    (net (code "88") (name "unconnected-(K1-NC-Pad5)") (class "Default")
      (node (ref "K1") (pin "5") (pinfunction "NC_5") (pintype "passive+no_connect"))
    )
  )
)
